# esp8266S_6A.net
KiCad netlist of a schematic drawn in EAGLE
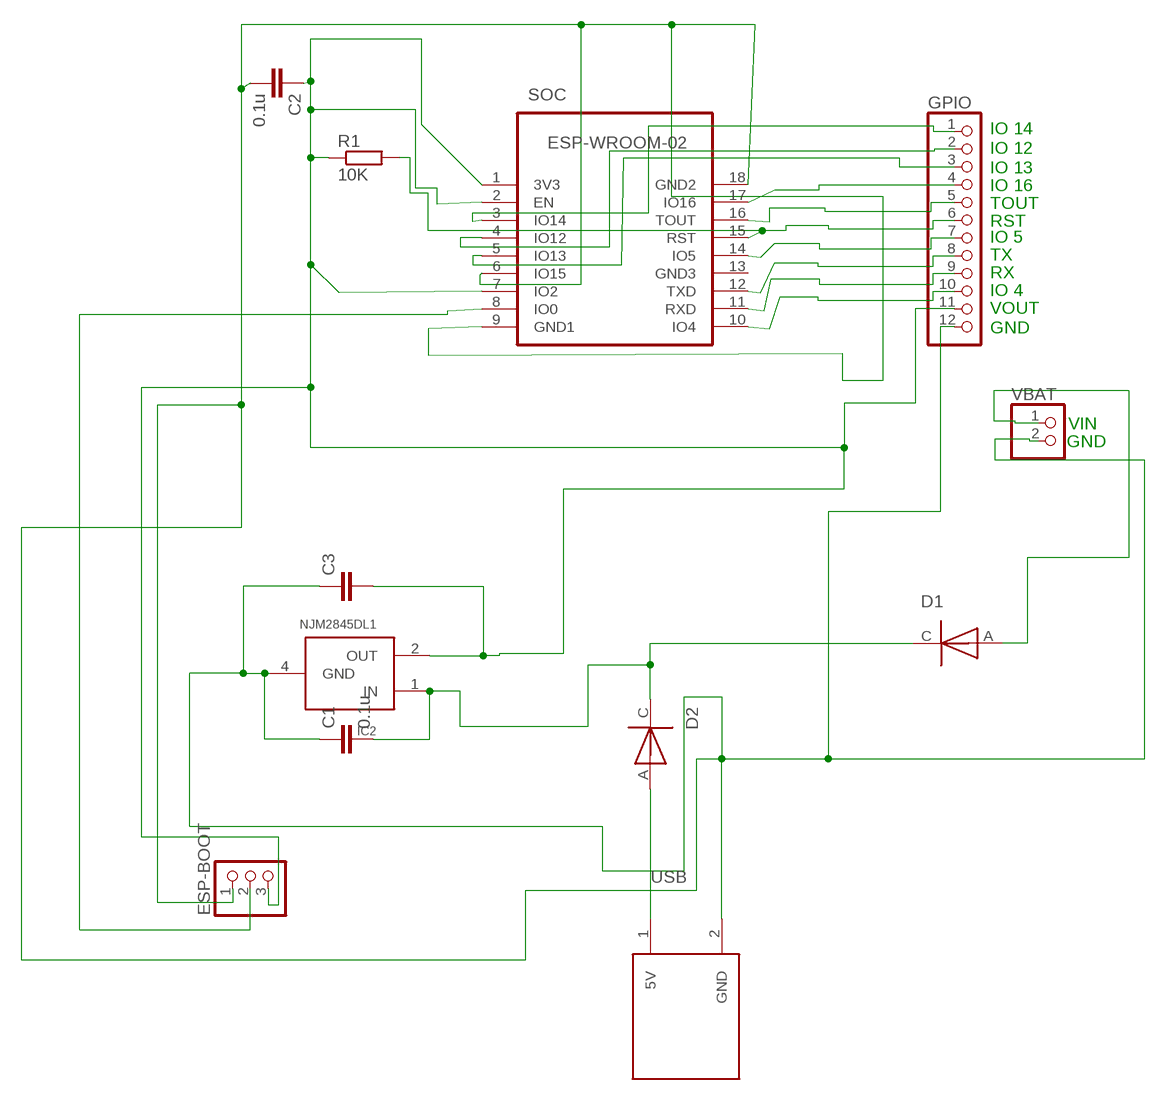
[diagram p0: schematic, sheet 1]

(export (version "E")
  (design (tool "Eeschema 10.0.6"))
  (components
    (comp (ref "C1")
      (value "0.1u")
      (footprint "eagle-import:C0603")
      (libsource (lib "eagle-import") (part "C-EUC0603"))
    )
    (comp (ref "C2")
      (value "0.1u")
      (footprint "eagle-import:C0603")
      (libsource (lib "eagle-import") (part "C-EUC0603"))
    )
    (comp (ref "C3")
      (value "C-EUC1206")
      (footprint "eagle-import:C1206")
      (libsource (lib "eagle-import") (part "C-EUC1206"))
    )
    (comp (ref "D1")
      (value "DIODE-EX")
      (footprint "eagle-import:SOD80C")
      (libsource (lib "eagle-import") (part "DIODE-EX"))
    )
    (comp (ref "D2")
      (value "DIODE-EX")
      (footprint "eagle-import:SOD80C")
      (libsource (lib "eagle-import") (part "DIODE-EX"))
    )
    (comp (ref "ESP-BOOT")
      (value "PINHD-1X3")
      (footprint "eagle-import:1X03")
      (libsource (lib "eagle-import") (part "PINHD-1X3"))
    )
    (comp (ref "GPIO")
      (value "PINHD-1X12")
      (footprint "eagle-import:1X12")
      (libsource (lib "eagle-import") (part "PINHD-1X12"))
    )
    (comp (ref "IC2")
      (value "NJM2845DL1")
      (footprint "eagle-import:NJM2845DL1-PKG")
      (libsource (lib "eagle-import") (part "NJM2845DL1"))
    )
    (comp (ref "R1")
      (value "10K")
      (footprint "eagle-import:R0603")
      (libsource (lib "eagle-import") (part "R-EU_R0603"))
    )
    (comp (ref "SOC")
      (value "ESP-WROOM-02")
      (footprint "eagle-import:FRONT-FACE-CP2")
      (libsource (lib "eagle-import") (part "ESP-WROOM-02-CP2FRONT"))
    )
    (comp (ref "USB")
      (value "USB-CUST-1")
      (footprint "eagle-import:USB-CUST-1-PKG")
      (libsource (lib "eagle-import") (part "USB-CUST-1"))
    )
    (comp (ref "VBAT")
      (value "PINHD-1X2")
      (footprint "eagle-import:1X02")
      (libsource (lib "eagle-import") (part "PINHD-1X2"))
    )
  )
  (nets
    (net (code "1") (name "Net-(D1-PadA)") (class "Default")
      (node (ref "D1") (pin "A") (pinfunction "A_A") (pintype "bidirectional"))
      (node (ref "VBAT") (pin "1") (pinfunction "1_1") (pintype "passive"))
    )
    (net (code "2") (name "Net-(IC2-GND)") (class "Default")
      (node (ref "C1") (pin "1") (pinfunction "1_1") (pintype "passive"))
      (node (ref "C2") (pin "2") (pinfunction "2_2") (pintype "passive"))
      (node (ref "C3") (pin "1") (pinfunction "1_1") (pintype "passive"))
      (node (ref "ESP-BOOT") (pin "1") (pinfunction "1_1") (pintype "passive"))
      (node (ref "GPIO") (pin "12") (pinfunction "12_12") (pintype "passive"))
      (node (ref "IC2") (pin "4") (pinfunction "GND_4") (pintype "bidirectional"))
      (node (ref "SOC") (pin "18") (pinfunction "GND2_18") (pintype "bidirectional"))
      (node (ref "SOC") (pin "6") (pinfunction "IO15_6") (pintype "bidirectional"))
      (node (ref "SOC") (pin "9") (pinfunction "GND1_9") (pintype "bidirectional"))
      (node (ref "USB") (pin "2") (pinfunction "GND_2") (pintype "bidirectional"))
      (node (ref "VBAT") (pin "2") (pinfunction "2_2") (pintype "passive"))
    )
    (net (code "3") (name "Net-(IC2-IN)") (class "Default")
      (node (ref "C1") (pin "2") (pinfunction "2_2") (pintype "passive"))
      (node (ref "D1") (pin "C") (pinfunction "C_C") (pintype "bidirectional"))
      (node (ref "D2") (pin "C") (pinfunction "C_C") (pintype "bidirectional"))
      (node (ref "IC2") (pin "1") (pinfunction "IN_1") (pintype "bidirectional"))
    )
    (net (code "4") (name "Net-(IC2-OUT)") (class "Default")
      (node (ref "C2") (pin "1") (pinfunction "1_1") (pintype "passive"))
      (node (ref "C3") (pin "2") (pinfunction "2_2") (pintype "passive"))
      (node (ref "ESP-BOOT") (pin "3") (pinfunction "3_3") (pintype "passive"))
      (node (ref "GPIO") (pin "11") (pinfunction "11_11") (pintype "passive"))
      (node (ref "IC2") (pin "2") (pinfunction "OUT_2") (pintype "bidirectional"))
      (node (ref "R1") (pin "1") (pinfunction "1_1") (pintype "passive"))
      (node (ref "SOC") (pin "1") (pinfunction "3V3_1") (pintype "bidirectional"))
      (node (ref "SOC") (pin "2") (pinfunction "EN_2") (pintype "bidirectional"))
      (node (ref "SOC") (pin "7") (pinfunction "IO2_7") (pintype "bidirectional"))
    )
    (net (code "5") (name "Net-(SOC-IO0)") (class "Default")
      (node (ref "ESP-BOOT") (pin "2") (pinfunction "2_2") (pintype "passive"))
      (node (ref "SOC") (pin "8") (pinfunction "IO0_8") (pintype "bidirectional"))
    )
    (net (code "6") (name "Net-(SOC-IO4)") (class "Default")
      (node (ref "GPIO") (pin "10") (pinfunction "10_10") (pintype "passive"))
      (node (ref "SOC") (pin "10") (pinfunction "IO4_10") (pintype "bidirectional"))
    )
    (net (code "7") (name "Net-(SOC-IO5)") (class "Default")
      (node (ref "GPIO") (pin "7") (pinfunction "7_7") (pintype "passive"))
      (node (ref "SOC") (pin "14") (pinfunction "IO5_14") (pintype "bidirectional"))
    )
    (net (code "8") (name "Net-(SOC-IO12)") (class "Default")
      (node (ref "GPIO") (pin "2") (pinfunction "2_2") (pintype "passive"))
      (node (ref "SOC") (pin "4") (pinfunction "IO12_4") (pintype "bidirectional"))
    )
    (net (code "9") (name "Net-(SOC-IO13)") (class "Default")
      (node (ref "GPIO") (pin "3") (pinfunction "3_3") (pintype "passive"))
      (node (ref "SOC") (pin "5") (pinfunction "IO13_5") (pintype "open_collector"))
    )
    (net (code "10") (name "Net-(SOC-IO14)") (class "Default")
      (node (ref "GPIO") (pin "1") (pinfunction "1_1") (pintype "passive"))
      (node (ref "SOC") (pin "3") (pinfunction "IO14_3") (pintype "bidirectional"))
    )
    (net (code "11") (name "Net-(SOC-IO16)") (class "Default")
      (node (ref "GPIO") (pin "4") (pinfunction "4_4") (pintype "passive"))
      (node (ref "SOC") (pin "17") (pinfunction "IO16_17") (pintype "bidirectional"))
    )
    (net (code "12") (name "Net-(SOC-RST)") (class "Default")
      (node (ref "GPIO") (pin "6") (pinfunction "6_6") (pintype "passive"))
      (node (ref "R1") (pin "2") (pinfunction "2_2") (pintype "passive"))
      (node (ref "SOC") (pin "15") (pinfunction "RST_15") (pintype "bidirectional"))
    )
    (net (code "13") (name "Net-(SOC-RXD)") (class "Default")
      (node (ref "GPIO") (pin "9") (pinfunction "9_9") (pintype "passive"))
      (node (ref "SOC") (pin "11") (pinfunction "RXD_11") (pintype "bidirectional"))
    )
    (net (code "14") (name "Net-(SOC-TOUT)") (class "Default")
      (node (ref "GPIO") (pin "5") (pinfunction "5_5") (pintype "passive"))
      (node (ref "SOC") (pin "16") (pinfunction "TOUT_16") (pintype "bidirectional"))
    )
    (net (code "15") (name "Net-(SOC-TXD)") (class "Default")
      (node (ref "GPIO") (pin "8") (pinfunction "8_8") (pintype "passive"))
      (node (ref "SOC") (pin "12") (pinfunction "TXD_12") (pintype "bidirectional"))
    )
    (net (code "16") (name "Net-(USB-5V)") (class "Default")
      (node (ref "D2") (pin "A") (pinfunction "A_A") (pintype "bidirectional"))
      (node (ref "USB") (pin "1") (pinfunction "5V_1") (pintype "bidirectional"))
    )
    (net (code "17") (name "unconnected-(SOC-GND3-Pad13)") (class "Default")
      (node (ref "SOC") (pin "13") (pinfunction "GND3_13") (pintype "bidirectional"))
    )
  )
)
